# power_electronics7.net
KiCad netlist of a schematic drawn in EAGLE
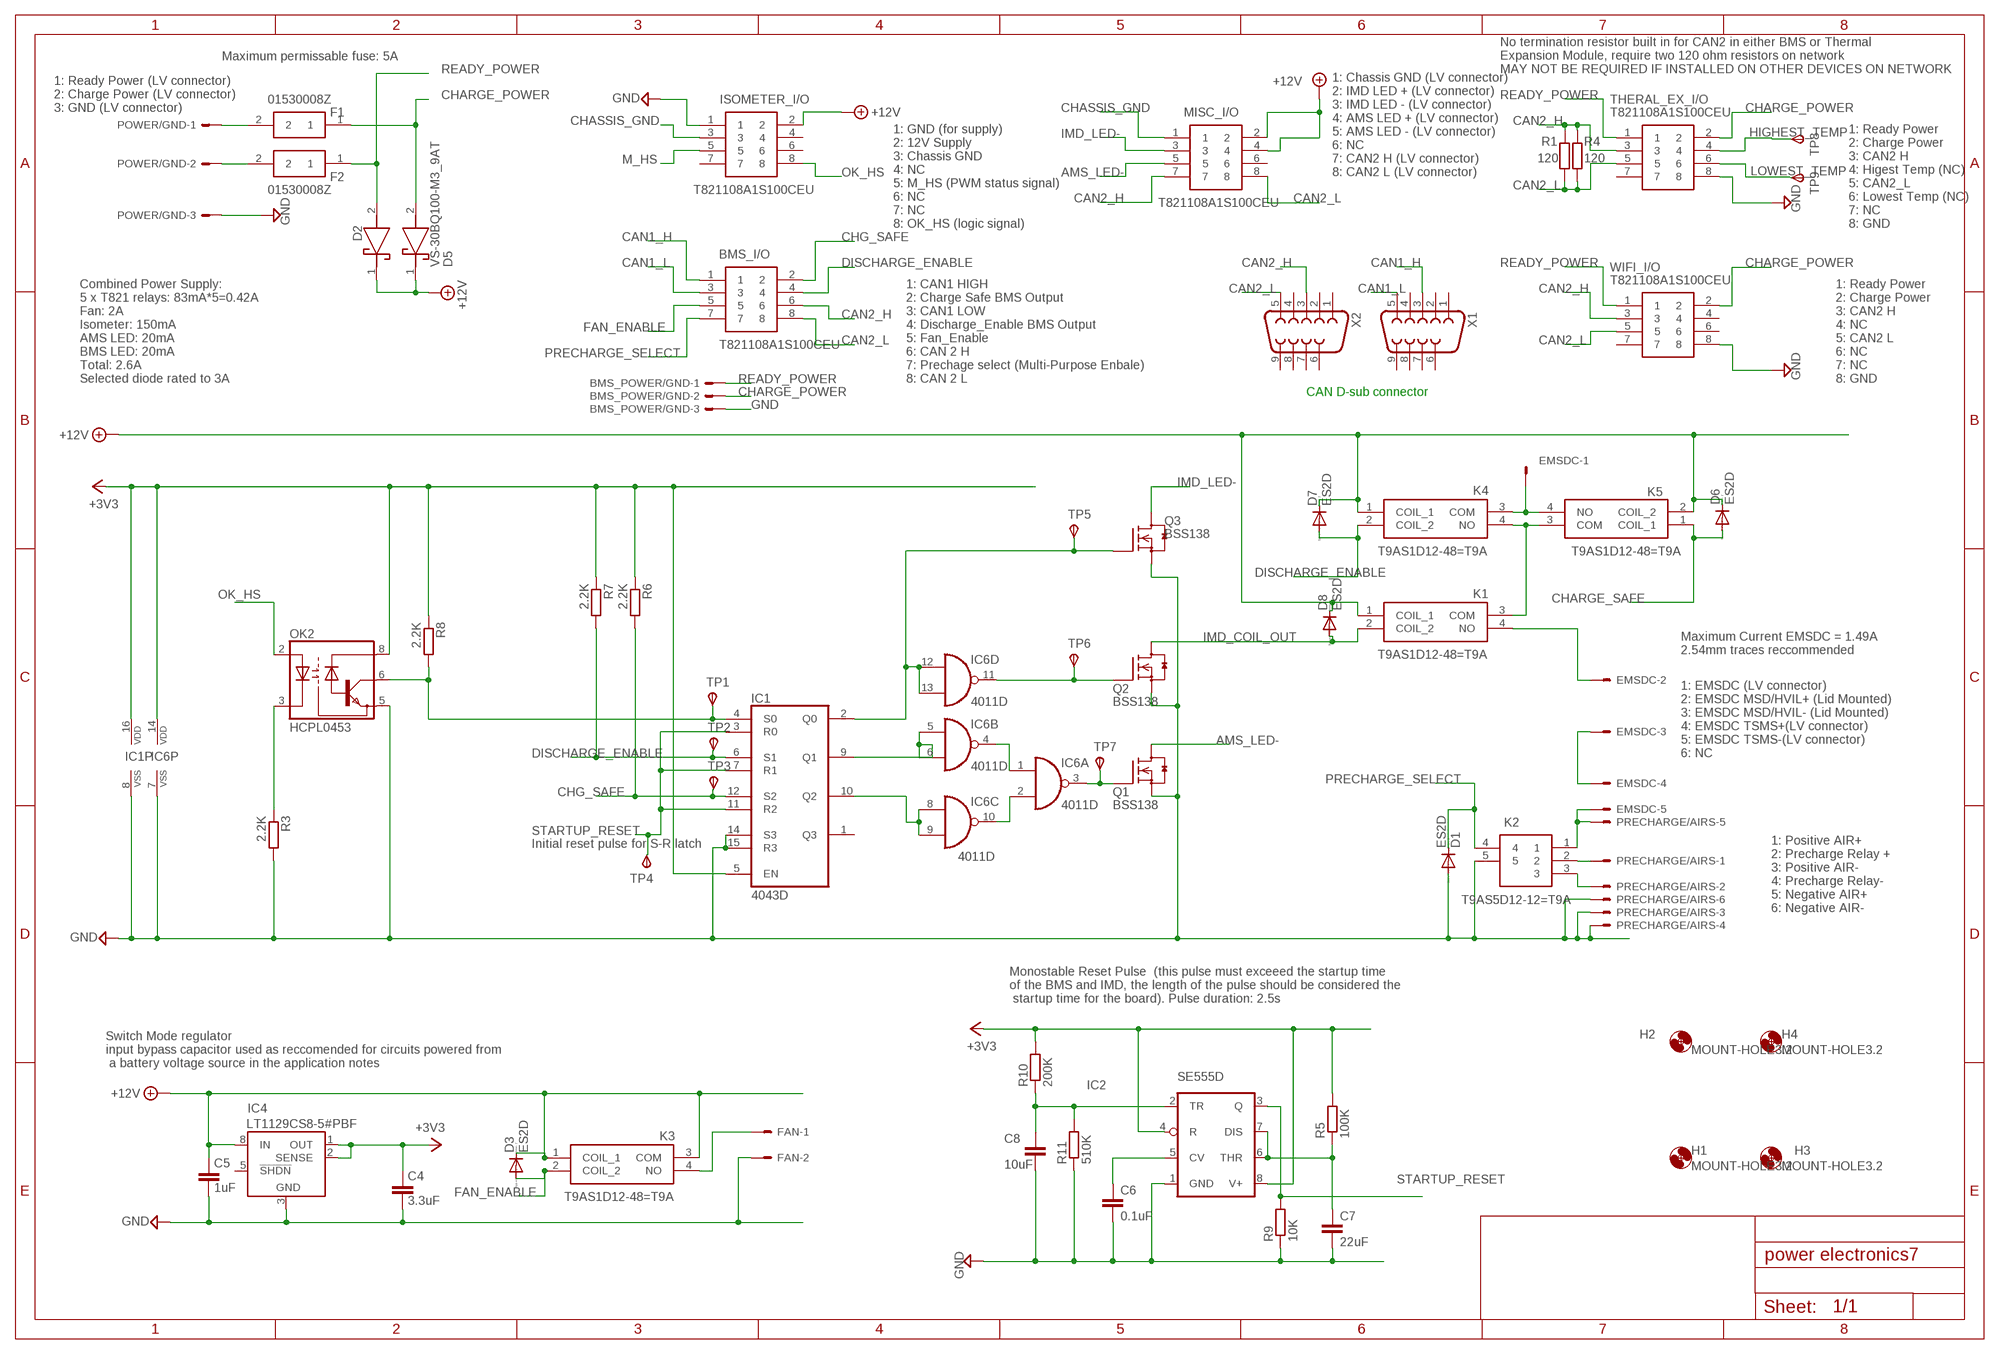
[diagram p0: schematic, sheet 1]

(export (version "E")
  (design (tool "Eeschema 10.0.6"))
  (components
    (comp (ref "BMS_I/O")
      (value "T821108A1S100CEU")
      (footprint "eagle-import:HDRV8W64P254_2X4_1778X895X915P")
      (fields (field (name "RS_PART_NUMBER") "8323569"))
      (libsource (lib "eagle-import") (part "T821108A1S100CEU"))
    )
    (comp (ref "BMS_POWER/GND")
      (value "KK-156-3")
      (footprint "eagle-import:KK-156-3")
      (fields (field (name "MF") "MOLEX"))
      (libsource (lib "eagle-import") (part "KK-156-3"))
    )
    (comp (ref "C4")
      (value "3.3uF")
      (footprint "eagle-import:C1206")
      (libsource (lib "eagle-import") (part "C-EUC1206"))
    )
    (comp (ref "C5")
      (value "1uF")
      (footprint "eagle-import:C1206")
      (libsource (lib "eagle-import") (part "C-EUC1206"))
    )
    (comp (ref "C6")
      (value "0.1uF")
      (footprint "eagle-import:C1206")
      (libsource (lib "eagle-import") (part "C-EUC1206"))
    )
    (comp (ref "C7")
      (value "22uF")
      (footprint "eagle-import:C1206")
      (libsource (lib "eagle-import") (part "C-EUC1206"))
    )
    (comp (ref "C8")
      (value "10uF")
      (footprint "eagle-import:C1206")
      (libsource (lib "eagle-import") (part "C-EUC1206"))
    )
    (comp (ref "D1")
      (value "ES2D")
      (footprint "eagle-import:SMB")
      (libsource (lib "eagle-import") (part "ES2D"))
    )
    (comp (ref "D2")
      (value "VS-30BQ100-M3_9AT")
      (footprint "eagle-import:DIOM7959X262N")
      (fields
        (field (name "MANUFACTURER_PART_NUMBER") "VS-30BQ100-M3/9AT")
        (field (name "MOUSER_PART_NUMBER") "78-VS-30BQ100-M39AT")
      )
      (libsource (lib "eagle-import") (part "VS-30BQ100-M3_9AT"))
    )
    (comp (ref "D3")
      (value "ES2D")
      (footprint "eagle-import:SMB")
      (libsource (lib "eagle-import") (part "ES2D"))
    )
    (comp (ref "D5")
      (value "VS-30BQ100-M3_9AT")
      (footprint "eagle-import:DIOM7959X262N")
      (fields
        (field (name "MANUFACTURER_PART_NUMBER") "VS-30BQ100-M3/9AT")
        (field (name "MOUSER_PART_NUMBER") "78-VS-30BQ100-M39AT")
      )
      (libsource (lib "eagle-import") (part "VS-30BQ100-M3_9AT"))
    )
    (comp (ref "D6")
      (value "ES2D")
      (footprint "eagle-import:SMB")
      (libsource (lib "eagle-import") (part "ES2D"))
    )
    (comp (ref "D7")
      (value "ES2D")
      (footprint "eagle-import:SMB")
      (libsource (lib "eagle-import") (part "ES2D"))
    )
    (comp (ref "D8")
      (value "ES2D")
      (footprint "eagle-import:SMB")
      (libsource (lib "eagle-import") (part "ES2D"))
    )
    (comp (ref "EMSDC")
      (value "KK-156-6")
      (footprint "eagle-import:KK-156-6")
      (fields (field (name "MF") "MOLEX"))
      (libsource (lib "eagle-import") (part "KK-156-6"))
    )
    (comp (ref "F1")
      (value "01530008Z")
      (footprint "eagle-import:01530008")
      (fields (field (name "RS_PART_NUMBER") "3607317"))
      (libsource (lib "eagle-import") (part "01530008Z"))
    )
    (comp (ref "F2")
      (value "01530008Z")
      (footprint "eagle-import:01530008")
      (fields (field (name "RS_PART_NUMBER") "3607317"))
      (libsource (lib "eagle-import") (part "01530008Z"))
    )
    (comp (ref "FAN")
      (value "KK-156-2")
      (footprint "eagle-import:KK-156-2")
      (fields (field (name "MF") "MOLEX"))
      (libsource (lib "eagle-import") (part "KK-156-2"))
    )
    (comp (ref "H1")
      (value "MOUNT-HOLE3.2")
      (footprint "eagle-import:3,2")
      (libsource (lib "eagle-import") (part "MOUNT-HOLE3.2"))
    )
    (comp (ref "H2")
      (value "MOUNT-HOLE3.2")
      (footprint "eagle-import:3,2")
      (libsource (lib "eagle-import") (part "MOUNT-HOLE3.2"))
    )
    (comp (ref "H3")
      (value "MOUNT-HOLE3.2")
      (footprint "eagle-import:3,2")
      (libsource (lib "eagle-import") (part "MOUNT-HOLE3.2"))
    )
    (comp (ref "H4")
      (value "MOUNT-HOLE3.2")
      (footprint "eagle-import:3,2")
      (libsource (lib "eagle-import") (part "MOUNT-HOLE3.2"))
    )
    (comp (ref "IC1")
      (value "4043D")
      (footprint "eagle-import:SO16")
      (libsource (lib "eagle-import") (part "4043D"))
    )
    (comp (ref "IC2")
      (value "SE555D")
      (footprint "eagle-import:SO08")
      (libsource (lib "eagle-import") (part "555DSE"))
    )
    (comp (ref "IC4")
      (value "LT1129CS8")
      (footprint "eagle-import:SOIC8")
      (fields (field (name "MPN") "LT1129CS8-5#PBF"))
      (libsource (lib "eagle-import") (part "LT1129CS8"))
    )
    (comp (ref "IC6")
      (value "4011D")
      (footprint "eagle-import:SO14")
      (libsource (lib "eagle-import") (part "4011D"))
    )
    (comp (ref "ISOMETER_I/O")
      (value "T821108A1S100CEU")
      (footprint "eagle-import:HDRV8W64P254_2X4_1778X895X915P")
      (fields (field (name "RS_PART_NUMBER") "8323569"))
      (libsource (lib "eagle-import") (part "T821108A1S100CEU"))
    )
    (comp (ref "K1")
      (value "T9AS1D12-48=T9A")
      (footprint "eagle-import:T9AS1D1248T9A")
      (fields (field (name "RS_PART_NUMBER") "6802534P"))
      (libsource (lib "eagle-import") (part "T9AS1D12-48=T9A"))
    )
    (comp (ref "K2")
      (value "T9AS5D12-12=T9A")
      (footprint "eagle-import:T9AS1D12")
      (fields (field (name "RS_PART_NUMBER") "6802528"))
      (libsource (lib "eagle-import") (part "T9AS5D12-12=T9A"))
    )
    (comp (ref "K3")
      (value "T9AS1D12-48=T9A")
      (footprint "eagle-import:T9AS1D1248T9A")
      (fields (field (name "RS_PART_NUMBER") "6802534P"))
      (libsource (lib "eagle-import") (part "T9AS1D12-48=T9A"))
    )
    (comp (ref "K4")
      (value "T9AS1D12-48=T9A")
      (footprint "eagle-import:T9AS1D1248T9A")
      (fields (field (name "RS_PART_NUMBER") "6802534P"))
      (libsource (lib "eagle-import") (part "T9AS1D12-48=T9A"))
    )
    (comp (ref "K5")
      (value "T9AS1D12-48=T9A")
      (footprint "eagle-import:T9AS1D1248T9A")
      (fields (field (name "RS_PART_NUMBER") "6802534P"))
      (libsource (lib "eagle-import") (part "T9AS1D12-48=T9A"))
    )
    (comp (ref "MISC_I/O")
      (value "T821108A1S100CEU")
      (footprint "eagle-import:HDRV8W64P254_2X4_1778X895X915P")
      (fields (field (name "RS_PART_NUMBER") "8323569"))
      (libsource (lib "eagle-import") (part "T821108A1S100CEU"))
    )
    (comp (ref "OK2")
      (value "HCPL0453")
      (footprint "eagle-import:SOIC08")
      (fields (field (name "MF") "AGILENT TECHNOLOGIES") (field (name "MPN") "HCPL-0453-000E"))
      (libsource (lib "eagle-import") (part "HCPL0453"))
    )
    (comp (ref "POWER/GND")
      (value "KK-156-3")
      (footprint "eagle-import:KK-156-3")
      (fields (field (name "MF") "MOLEX"))
      (libsource (lib "eagle-import") (part "KK-156-3"))
    )
    (comp (ref "PRECHARGE/AIRS")
      (value "KK-156-6")
      (footprint "eagle-import:KK-156-6")
      (fields (field (name "MF") "MOLEX"))
      (libsource (lib "eagle-import") (part "KK-156-6"))
    )
    (comp (ref "Q1")
      (value "BSS138")
      (footprint "eagle-import:SOT23")
      (libsource (lib "eagle-import") (part "BSS138"))
    )
    (comp (ref "Q2")
      (value "BSS138")
      (footprint "eagle-import:SOT23")
      (libsource (lib "eagle-import") (part "BSS138"))
    )
    (comp (ref "Q3")
      (value "BSS138")
      (footprint "eagle-import:SOT23")
      (libsource (lib "eagle-import") (part "BSS138"))
    )
    (comp (ref "R1")
      (value "120")
      (footprint "eagle-import:R1206")
      (libsource (lib "eagle-import") (part "R-EU_R1206"))
    )
    (comp (ref "R3")
      (value "2.2K")
      (footprint "eagle-import:R1206")
      (libsource (lib "eagle-import") (part "R-EU_R1206"))
    )
    (comp (ref "R4")
      (value "120")
      (footprint "eagle-import:R1206")
      (libsource (lib "eagle-import") (part "R-EU_R1206"))
    )
    (comp (ref "R5")
      (value "100K")
      (footprint "eagle-import:R1206")
      (libsource (lib "eagle-import") (part "R-EU_R1206"))
    )
    (comp (ref "R6")
      (value "2.2K")
      (footprint "eagle-import:R1206")
      (libsource (lib "eagle-import") (part "R-EU_R1206"))
    )
    (comp (ref "R7")
      (value "2.2K")
      (footprint "eagle-import:R1206")
      (libsource (lib "eagle-import") (part "R-EU_R1206"))
    )
    (comp (ref "R8")
      (value "2.2K")
      (footprint "eagle-import:R1206")
      (libsource (lib "eagle-import") (part "R-EU_R1206"))
    )
    (comp (ref "R9")
      (value "10K")
      (footprint "eagle-import:R1206")
      (libsource (lib "eagle-import") (part "R-EU_R1206"))
    )
    (comp (ref "R10")
      (value "200K")
      (footprint "eagle-import:R1206")
      (libsource (lib "eagle-import") (part "R-EU_R1206"))
    )
    (comp (ref "R11")
      (value "510K")
      (footprint "eagle-import:R1206")
      (libsource (lib "eagle-import") (part "R-EU_R1206"))
    )
    (comp (ref "THERAL_EX_I/O")
      (value "T821108A1S100CEU")
      (footprint "eagle-import:HDRV8W64P254_2X4_1778X895X915P")
      (fields (field (name "RS_PART_NUMBER") "8323569"))
      (libsource (lib "eagle-import") (part "T821108A1S100CEU"))
    )
    (comp (ref "TP1")
      (value "TPSTP11R")
      (footprint "eagle-import:TP11R")
      (libsource (lib "eagle-import") (part "TPSTP11R"))
    )
    (comp (ref "TP2")
      (value "TPSTP11R")
      (footprint "eagle-import:TP11R")
      (libsource (lib "eagle-import") (part "TPSTP11R"))
    )
    (comp (ref "TP3")
      (value "TPSTP11R")
      (footprint "eagle-import:TP11R")
      (libsource (lib "eagle-import") (part "TPSTP11R"))
    )
    (comp (ref "TP4")
      (value "TPSTP11R")
      (footprint "eagle-import:TP11R")
      (libsource (lib "eagle-import") (part "TPSTP11R"))
    )
    (comp (ref "TP5")
      (value "TPSTP11R")
      (footprint "eagle-import:TP11R")
      (libsource (lib "eagle-import") (part "TPSTP11R"))
    )
    (comp (ref "TP6")
      (value "TPSTP11R")
      (footprint "eagle-import:TP11R")
      (libsource (lib "eagle-import") (part "TPSTP11R"))
    )
    (comp (ref "TP7")
      (value "TPSTP11R")
      (footprint "eagle-import:TP11R")
      (libsource (lib "eagle-import") (part "TPSTP11R"))
    )
    (comp (ref "TP8")
      (value "TPSTP11R")
      (footprint "eagle-import:TP11R")
      (libsource (lib "eagle-import") (part "TPSTP11R"))
    )
    (comp (ref "TP9")
      (value "TPSTP11R")
      (footprint "eagle-import:TP11R")
      (libsource (lib "eagle-import") (part "TPSTP11R"))
    )
    (comp (ref "WIFI_I/O")
      (value "T821108A1S100CEU")
      (footprint "eagle-import:HDRV8W64P254_2X4_1778X895X915P")
      (fields (field (name "RS_PART_NUMBER") "8323569"))
      (libsource (lib "eagle-import") (part "T821108A1S100CEU"))
    )
    (comp (ref "X1")
      (value "F09V")
      (footprint "eagle-import:F09V")
      (libsource (lib "eagle-import") (part "F09V"))
    )
    (comp (ref "X2")
      (value "F09V")
      (footprint "eagle-import:F09V")
      (libsource (lib "eagle-import") (part "F09V"))
    )
  )
  (nets
    (net (code "1") (name "+3V3") (class "Default")
      (node (ref "C4") (pin "1") (pinfunction "1_1") (pintype "passive"))
      (node (ref "IC1") (pin "16") (pinfunction "VDD_16") (pintype "power_in"))
      (node (ref "IC1") (pin "5") (pinfunction "EN_5") (pintype "input"))
      (node (ref "IC2") (pin "4") (pinfunction "R_4") (pintype "input"))
      (node (ref "IC2") (pin "8") (pinfunction "V+_8") (pintype "power_in"))
      (node (ref "IC4") (pin "1") (pinfunction "OUT_1") (pintype "output"))
      (node (ref "IC4") (pin "2") (pinfunction "SENSE_2") (pintype "input"))
      (node (ref "IC6") (pin "14") (pinfunction "VDD_14") (pintype "power_in"))
      (node (ref "OK2") (pin "8") (pinfunction "VCC_8") (pintype "passive"))
      (node (ref "R10") (pin "2") (pinfunction "2_2") (pintype "passive"))
      (node (ref "R5") (pin "2") (pinfunction "2_2") (pintype "passive"))
      (node (ref "R6") (pin "1") (pinfunction "1_1") (pintype "passive"))
      (node (ref "R7") (pin "1") (pinfunction "1_1") (pintype "passive"))
      (node (ref "R8") (pin "1") (pinfunction "1_1") (pintype "passive"))
    )
    (net (code "2") (name "+12V") (class "Default")
      (node (ref "C5") (pin "1") (pinfunction "1_1") (pintype "passive"))
      (node (ref "D2") (pin "1") (pinfunction "K_1") (pintype "bidirectional"))
      (node (ref "D3") (pin "C") (pinfunction "C_C") (pintype "passive"))
      (node (ref "D5") (pin "1") (pinfunction "K_1") (pintype "bidirectional"))
      (node (ref "D6") (pin "C") (pinfunction "C_C") (pintype "passive"))
      (node (ref "D7") (pin "C") (pinfunction "C_C") (pintype "passive"))
      (node (ref "D8") (pin "C") (pinfunction "C_C") (pintype "passive"))
      (node (ref "IC4") (pin "8") (pinfunction "IN_8") (pintype "input"))
      (node (ref "ISOMETER_I/O") (pin "2") (pinfunction "2_2") (pintype "bidirectional"))
      (node (ref "K1") (pin "1") (pinfunction "COIL_1_1") (pintype "bidirectional"))
      (node (ref "K3") (pin "1") (pinfunction "COIL_1_1") (pintype "bidirectional"))
      (node (ref "K3") (pin "3") (pinfunction "COM_3") (pintype "bidirectional"))
      (node (ref "K4") (pin "1") (pinfunction "COIL_1_1") (pintype "bidirectional"))
      (node (ref "K5") (pin "2") (pinfunction "COIL_2_2") (pintype "bidirectional"))
      (node (ref "MISC_I/O") (pin "2") (pinfunction "2_2") (pintype "bidirectional"))
      (node (ref "MISC_I/O") (pin "4") (pinfunction "4_4") (pintype "bidirectional"))
    )
    (net (code "3") (name "/AMS_LED-") (class "Default")
      (node (ref "MISC_I/O") (pin "5") (pinfunction "5_5") (pintype "bidirectional"))
      (node (ref "Q1") (pin "3") (pinfunction "D_3") (pintype "passive"))
    )
    (net (code "4") (name "/CAN1_H") (class "Default")
      (node (ref "BMS_I/O") (pin "1") (pinfunction "1_1") (pintype "bidirectional"))
      (node (ref "X1") (pin "3") (pinfunction "3_3") (pintype "passive"))
    )
    (net (code "5") (name "/CAN1_L") (class "Default")
      (node (ref "BMS_I/O") (pin "3") (pinfunction "3_3") (pintype "bidirectional"))
      (node (ref "X1") (pin "5") (pinfunction "5_5") (pintype "passive"))
    )
    (net (code "6") (name "/CAN2_H") (class "Default")
      (node (ref "BMS_I/O") (pin "6") (pinfunction "6_6") (pintype "bidirectional"))
      (node (ref "MISC_I/O") (pin "7") (pinfunction "7_7") (pintype "bidirectional"))
      (node (ref "R1") (pin "1") (pinfunction "1_1") (pintype "passive"))
      (node (ref "R4") (pin "1") (pinfunction "1_1") (pintype "passive"))
      (node (ref "THERAL_EX_I/O") (pin "3") (pinfunction "3_3") (pintype "bidirectional"))
      (node (ref "WIFI_I/O") (pin "3") (pinfunction "3_3") (pintype "bidirectional"))
      (node (ref "X2") (pin "3") (pinfunction "3_3") (pintype "passive"))
    )
    (net (code "7") (name "/CAN2_L") (class "Default")
      (node (ref "BMS_I/O") (pin "8") (pinfunction "8_8") (pintype "bidirectional"))
      (node (ref "MISC_I/O") (pin "8") (pinfunction "8_8") (pintype "bidirectional"))
      (node (ref "R1") (pin "2") (pinfunction "2_2") (pintype "passive"))
      (node (ref "R4") (pin "2") (pinfunction "2_2") (pintype "passive"))
      (node (ref "THERAL_EX_I/O") (pin "5") (pinfunction "5_5") (pintype "bidirectional"))
      (node (ref "WIFI_I/O") (pin "5") (pinfunction "5_5") (pintype "bidirectional"))
      (node (ref "X2") (pin "5") (pinfunction "5_5") (pintype "passive"))
    )
    (net (code "8") (name "/CHARGE_POWER") (class "Default")
      (node (ref "BMS_POWER/GND") (pin "2") (pinfunction "S_2") (pintype "passive"))
      (node (ref "D5") (pin "2") (pinfunction "A_2") (pintype "bidirectional"))
      (node (ref "F1") (pin "1") (pinfunction "1_1") (pintype "bidirectional"))
      (node (ref "THERAL_EX_I/O") (pin "2") (pinfunction "2_2") (pintype "bidirectional"))
      (node (ref "WIFI_I/O") (pin "2") (pinfunction "2_2") (pintype "bidirectional"))
    )
    (net (code "9") (name "/CHARGE_SAFE") (class "Default")
      (node (ref "D6") (pin "A") (pinfunction "A_A") (pintype "passive"))
      (node (ref "K5") (pin "1") (pinfunction "COIL_1_1") (pintype "bidirectional"))
    )
    (net (code "10") (name "/CHASSIS_GND") (class "Default")
      (node (ref "ISOMETER_I/O") (pin "3") (pinfunction "3_3") (pintype "bidirectional"))
      (node (ref "MISC_I/O") (pin "1") (pinfunction "1_1") (pintype "bidirectional"))
    )
    (net (code "11") (name "/CHG_SAFE") (class "Default")
      (node (ref "BMS_I/O") (pin "2") (pinfunction "2_2") (pintype "bidirectional"))
      (node (ref "IC1") (pin "12") (pinfunction "S2_12") (pintype "input"))
      (node (ref "R6") (pin "2") (pinfunction "2_2") (pintype "passive"))
      (node (ref "TP3") (pin "TP") (pinfunction "PP_TP") (pintype "input"))
    )
    (net (code "12") (name "/DISCHARGE_ENABLE") (class "Default")
      (node (ref "BMS_I/O") (pin "4") (pinfunction "4_4") (pintype "bidirectional"))
      (node (ref "D7") (pin "A") (pinfunction "A_A") (pintype "passive"))
      (node (ref "IC1") (pin "6") (pinfunction "S1_6") (pintype "input"))
      (node (ref "K4") (pin "2") (pinfunction "COIL_2_2") (pintype "bidirectional"))
      (node (ref "R7") (pin "2") (pinfunction "2_2") (pintype "passive"))
      (node (ref "TP2") (pin "TP") (pinfunction "PP_TP") (pintype "input"))
    )
    (net (code "13") (name "/FAN_ENABLE") (class "Default")
      (node (ref "BMS_I/O") (pin "5") (pinfunction "5_5") (pintype "bidirectional"))
      (node (ref "D3") (pin "A") (pinfunction "A_A") (pintype "passive"))
      (node (ref "K3") (pin "2") (pinfunction "COIL_2_2") (pintype "bidirectional"))
    )
    (net (code "14") (name "/HIGHEST_TEMP") (class "Default")
      (node (ref "THERAL_EX_I/O") (pin "4") (pinfunction "4_4") (pintype "bidirectional"))
      (node (ref "TP8") (pin "TP") (pinfunction "PP_TP") (pintype "input"))
    )
    (net (code "15") (name "/IMD_COIL_OUT") (class "Default")
      (node (ref "D8") (pin "A") (pinfunction "A_A") (pintype "passive"))
      (node (ref "K1") (pin "2") (pinfunction "COIL_2_2") (pintype "bidirectional"))
      (node (ref "Q2") (pin "3") (pinfunction "D_3") (pintype "passive"))
    )
    (net (code "16") (name "/IMD_LED-") (class "Default")
      (node (ref "MISC_I/O") (pin "3") (pinfunction "3_3") (pintype "bidirectional"))
      (node (ref "Q3") (pin "3") (pinfunction "D_3") (pintype "passive"))
    )
    (net (code "17") (name "/LOWEST_TEMP") (class "Default")
      (node (ref "THERAL_EX_I/O") (pin "6") (pinfunction "6_6") (pintype "bidirectional"))
      (node (ref "TP9") (pin "TP") (pinfunction "PP_TP") (pintype "input"))
    )
    (net (code "18") (name "/M_HS") (class "Default")
      (node (ref "ISOMETER_I/O") (pin "5") (pinfunction "5_5") (pintype "bidirectional"))
    )
    (net (code "19") (name "/OK_HS") (class "Default")
      (node (ref "ISOMETER_I/O") (pin "8") (pinfunction "8_8") (pintype "bidirectional"))
      (node (ref "OK2") (pin "2") (pinfunction "A_2") (pintype "passive"))
    )
    (net (code "20") (name "/PRECHARGE_SELECT") (class "Default")
      (node (ref "BMS_I/O") (pin "7") (pinfunction "7_7") (pintype "bidirectional"))
      (node (ref "D1") (pin "C") (pinfunction "C_C") (pintype "passive"))
      (node (ref "K2") (pin "4") (pinfunction "4_4") (pintype "bidirectional"))
    )
    (net (code "21") (name "/READY_POWER") (class "Default")
      (node (ref "BMS_POWER/GND") (pin "1") (pinfunction "S_1") (pintype "passive"))
      (node (ref "D2") (pin "2") (pinfunction "A_2") (pintype "bidirectional"))
      (node (ref "F2") (pin "1") (pinfunction "1_1") (pintype "bidirectional"))
      (node (ref "THERAL_EX_I/O") (pin "1") (pinfunction "1_1") (pintype "bidirectional"))
      (node (ref "WIFI_I/O") (pin "1") (pinfunction "1_1") (pintype "bidirectional"))
    )
    (net (code "22") (name "/STARTUP_RESET") (class "Default")
      (node (ref "IC1") (pin "11") (pinfunction "R2_11") (pintype "input"))
      (node (ref "IC1") (pin "3") (pinfunction "R0_3") (pintype "input"))
      (node (ref "IC1") (pin "7") (pinfunction "R1_7") (pintype "input"))
      (node (ref "IC2") (pin "3") (pinfunction "Q_3") (pintype "output"))
      (node (ref "R9") (pin "2") (pinfunction "2_2") (pintype "passive"))
      (node (ref "TP4") (pin "TP") (pinfunction "PP_TP") (pintype "input"))
    )
    (net (code "23") (name "GND") (class "Default")
      (node (ref "BMS_POWER/GND") (pin "3") (pinfunction "S_3") (pintype "passive"))
      (node (ref "C4") (pin "2") (pinfunction "2_2") (pintype "passive"))
      (node (ref "C5") (pin "2") (pinfunction "2_2") (pintype "passive"))
      (node (ref "C6") (pin "2") (pinfunction "2_2") (pintype "passive"))
      (node (ref "C7") (pin "2") (pinfunction "2_2") (pintype "passive"))
      (node (ref "C8") (pin "2") (pinfunction "2_2") (pintype "passive"))
      (node (ref "D1") (pin "A") (pinfunction "A_A") (pintype "passive"))
      (node (ref "FAN") (pin "2") (pinfunction "S_2") (pintype "passive"))
      (node (ref "IC1") (pin "14") (pinfunction "S3_14") (pintype "input"))
      (node (ref "IC1") (pin "15") (pinfunction "R3_15") (pintype "input"))
      (node (ref "IC1") (pin "8") (pinfunction "VSS_8") (pintype "power_in"))
      (node (ref "IC2") (pin "1") (pinfunction "GND_1") (pintype "power_in"))
      (node (ref "IC4") (pin "3") (pinfunction "GND_3") (pintype "power_in"))
      (node (ref "IC6") (pin "7") (pinfunction "VSS_7") (pintype "power_in"))
      (node (ref "ISOMETER_I/O") (pin "1") (pinfunction "1_1") (pintype "bidirectional"))
      (node (ref "K2") (pin "5") (pinfunction "5_5") (pintype "bidirectional"))
      (node (ref "OK2") (pin "5") (pinfunction "GND_5") (pintype "passive"))
      (node (ref "POWER/GND") (pin "3") (pinfunction "S_3") (pintype "passive"))
      (node (ref "PRECHARGE/AIRS") (pin "3") (pinfunction "S_3") (pintype "passive"))
      (node (ref "PRECHARGE/AIRS") (pin "4") (pinfunction "S_4") (pintype "passive"))
      (node (ref "PRECHARGE/AIRS") (pin "6") (pinfunction "S_6") (pintype "passive"))
      (node (ref "Q1") (pin "2") (pinfunction "S_2") (pintype "passive"))
      (node (ref "Q2") (pin "2") (pinfunction "S_2") (pintype "passive"))
      (node (ref "Q3") (pin "2") (pinfunction "S_2") (pintype "passive"))
      (node (ref "R11") (pin "1") (pinfunction "1_1") (pintype "passive"))
      (node (ref "R3") (pin "2") (pinfunction "2_2") (pintype "passive"))
      (node (ref "R9") (pin "1") (pinfunction "1_1") (pintype "passive"))
      (node (ref "THERAL_EX_I/O") (pin "8") (pinfunction "8_8") (pintype "bidirectional"))
      (node (ref "WIFI_I/O") (pin "8") (pinfunction "8_8") (pintype "bidirectional"))
    )
    (net (code "24") (name "Net-(EMSDCA-S)") (class "Default")
      (node (ref "EMSDC") (pin "1") (pinfunction "S_1") (pintype "passive"))
      (node (ref "K4") (pin "3") (pinfunction "COM_3") (pintype "bidirectional"))
      (node (ref "K5") (pin "4") (pinfunction "NO_4") (pintype "bidirectional"))
    )
    (net (code "25") (name "Net-(EMSDCB-S)") (class "Default")
      (node (ref "EMSDC") (pin "2") (pinfunction "S_2") (pintype "passive"))
      (node (ref "K1") (pin "4") (pinfunction "NO_4") (pintype "bidirectional"))
    )
    (net (code "26") (name "Net-(EMSDCC-S)") (class "Default")
      (node (ref "EMSDC") (pin "3") (pinfunction "S_3") (pintype "passive"))
      (node (ref "EMSDC") (pin "4") (pinfunction "S_4") (pintype "passive"))
    )
    (net (code "27") (name "Net-(EMSDCE-S)") (class "Default")
      (node (ref "EMSDC") (pin "5") (pinfunction "S_5") (pintype "passive"))
      (node (ref "K2") (pin "1") (pinfunction "1_1") (pintype "bidirectional"))
      (node (ref "PRECHARGE/AIRS") (pin "5") (pinfunction "S_5") (pintype "passive"))
    )
    (net (code "28") (name "Net-(FANA-S)") (class "Default")
      (node (ref "FAN") (pin "1") (pinfunction "S_1") (pintype "passive"))
      (node (ref "K3") (pin "4") (pinfunction "NO_4") (pintype "bidirectional"))
    )
    (net (code "29") (name "Net-(IC1A-Q0)") (class "Default")
      (node (ref "IC1") (pin "2") (pinfunction "Q0_2") (pintype "output"))
      (node (ref "IC6") (pin "12") (pinfunction "I0_12") (pintype "input"))
      (node (ref "IC6") (pin "13") (pinfunction "I1_13") (pintype "input"))
      (node (ref "Q3") (pin "1") (pinfunction "G_1") (pintype "passive"))
      (node (ref "TP5") (pin "TP") (pinfunction "PP_TP") (pintype "input"))
    )
    (net (code "30") (name "Net-(IC1A-Q1)") (class "Default")
      (node (ref "IC1") (pin "9") (pinfunction "Q1_9") (pintype "output"))
      (node (ref "IC6") (pin "5") (pinfunction "I0_5") (pintype "input"))
      (node (ref "IC6") (pin "6") (pinfunction "I1_6") (pintype "input"))
    )
    (net (code "31") (name "Net-(IC1A-Q2)") (class "Default")
      (node (ref "IC1") (pin "10") (pinfunction "Q2_10") (pintype "output"))
      (node (ref "IC6") (pin "8") (pinfunction "I0_8") (pintype "input"))
      (node (ref "IC6") (pin "9") (pinfunction "I1_9") (pintype "input"))
    )
    (net (code "32") (name "Net-(IC1A-S0)") (class "Default")
      (node (ref "IC1") (pin "4") (pinfunction "S0_4") (pintype "input"))
      (node (ref "OK2") (pin "6") (pinfunction "VO_6") (pintype "passive"))
      (node (ref "R8") (pin "2") (pinfunction "2_2") (pintype "passive"))
      (node (ref "TP1") (pin "TP") (pinfunction "PP_TP") (pintype "input"))
    )
    (net (code "33") (name "Net-(IC2-CV)") (class "Default")
      (node (ref "C6") (pin "1") (pinfunction "1_1") (pintype "passive"))
      (node (ref "IC2") (pin "5") (pinfunction "CV_5") (pintype "input"))
    )
    (net (code "34") (name "Net-(IC2-DIS)") (class "Default")
      (node (ref "C7") (pin "1") (pinfunction "1_1") (pintype "passive"))
      (node (ref "IC2") (pin "6") (pinfunction "THR_6") (pintype "input"))
      (node (ref "IC2") (pin "7") (pinfunction "DIS_7") (pintype "input"))
      (node (ref "R5") (pin "1") (pinfunction "1_1") (pintype "passive"))
    )
    (net (code "35") (name "Net-(IC2-TR)") (class "Default")
      (node (ref "C8") (pin "1") (pinfunction "1_1") (pintype "passive"))
      (node (ref "IC2") (pin "2") (pinfunction "TR_2") (pintype "input"))
      (node (ref "R10") (pin "1") (pinfunction "1_1") (pintype "passive"))
      (node (ref "R11") (pin "2") (pinfunction "2_2") (pintype "passive"))
    )
    (net (code "36") (name "Net-(IC6A-I0)") (class "Default")
      (node (ref "IC6") (pin "1") (pinfunction "I0_1") (pintype "input"))
      (node (ref "IC6") (pin "4") (pinfunction "O_4") (pintype "output"))
    )
    (net (code "37") (name "Net-(IC6A-I1)") (class "Default")
      (node (ref "IC6") (pin "10") (pinfunction "O_10") (pintype "output"))
      (node (ref "IC6") (pin "2") (pinfunction "I1_2") (pintype "input"))
    )
    (net (code "38") (name "Net-(IC6A-O)") (class "Default")
      (node (ref "IC6") (pin "3") (pinfunction "O_3") (pintype "output"))
      (node (ref "Q1") (pin "1") (pinfunction "G_1") (pintype "passive"))
      (node (ref "TP7") (pin "TP") (pinfunction "PP_TP") (pintype "input"))
    )
    (net (code "39") (name "Net-(IC6D-O)") (class "Default")
      (node (ref "IC6") (pin "11") (pinfunction "O_11") (pintype "output"))
      (node (ref "Q2") (pin "1") (pinfunction "G_1") (pintype "passive"))
      (node (ref "TP6") (pin "TP") (pinfunction "PP_TP") (pintype "input"))
    )
    (net (code "40") (name "Net-(K1-COM)") (class "Default")
      (node (ref "K1") (pin "3") (pinfunction "COM_3") (pintype "bidirectional"))
      (node (ref "K4") (pin "4") (pinfunction "NO_4") (pintype "bidirectional"))
      (node (ref "K5") (pin "3") (pinfunction "COM_3") (pintype "bidirectional"))
    )
    (net (code "41") (name "Net-(OK2-C)") (class "Default")
      (node (ref "OK2") (pin "3") (pinfunction "C_3") (pintype "passive"))
      (node (ref "R3") (pin "1") (pinfunction "1_1") (pintype "passive"))
    )
    (net (code "42") (name "Net-(POWER/GNDA-S)") (class "Default")
      (node (ref "F1") (pin "2") (pinfunction "2_2") (pintype "bidirectional"))
      (node (ref "POWER/GND") (pin "1") (pinfunction "S_1") (pintype "passive"))
    )
    (net (code "43") (name "Net-(POWER/GNDB-S)") (class "Default")
      (node (ref "F2") (pin "2") (pinfunction "2_2") (pintype "bidirectional"))
      (node (ref "POWER/GND") (pin "2") (pinfunction "S_2") (pintype "passive"))
    )
    (net (code "44") (name "Net-(PRECHARGE/AIRSA-S)") (class "Default")
      (node (ref "K2") (pin "2") (pinfunction "2_2") (pintype "bidirectional"))
      (node (ref "PRECHARGE/AIRS") (pin "1") (pinfunction "S_1") (pintype "passive"))
    )
    (net (code "45") (name "Net-(PRECHARGE/AIRSB-S)") (class "Default")
      (node (ref "K2") (pin "3") (pinfunction "3_3") (pintype "bidirectional"))
      (node (ref "PRECHARGE/AIRS") (pin "2") (pinfunction "S_2") (pintype "passive"))
    )
    (net (code "46") (name "unconnected-(IC1A-Q3-Pad1)") (class "Default")
      (node (ref "IC1") (pin "1") (pinfunction "Q3_1") (pintype "output"))
    )
    (net (code "47") (name "unconnected-(IC4A-~{SHDN}-Pad5)") (class "Default")
      (node (ref "IC4") (pin "5") (pinfunction "~{SHDN}_5") (pintype "input"))
    )
    (net (code "48") (name "unconnected-(ISOMETER_I/O-Pad4)") (class "Default")
      (node (ref "ISOMETER_I/O") (pin "4") (pinfunction "4_4") (pintype "bidirectional"))
    )
    (net (code "49") (name "unconnected-(ISOMETER_I/O-Pad6)") (class "Default")
      (node (ref "ISOMETER_I/O") (pin "6") (pinfunction "6_6") (pintype "bidirectional"))
    )
    (net (code "50") (name "unconnected-(ISOMETER_I/O-Pad7)") (class "Default")
      (node (ref "ISOMETER_I/O") (pin "7") (pinfunction "7_7") (pintype "bidirectional"))
    )
    (net (code "51") (name "unconnected-(MISC_I/O-Pad6)") (class "Default")
      (node (ref "MISC_I/O") (pin "6") (pinfunction "6_6") (pintype "bidirectional"))
    )
    (net (code "52") (name "unconnected-(THERAL_EX_I/O-Pad7)") (class "Default")
      (node (ref "THERAL_EX_I/O") (pin "7") (pinfunction "7_7") (pintype "bidirectional"))
    )
    (net (code "53") (name "unconnected-(WIFI_I/O-Pad4)") (class "Default")
      (node (ref "WIFI_I/O") (pin "4") (pinfunction "4_4") (pintype "bidirectional"))
    )
    (net (code "54") (name "unconnected-(WIFI_I/O-Pad6)") (class "Default")
      (node (ref "WIFI_I/O") (pin "6") (pinfunction "6_6") (pintype "bidirectional"))
    )
    (net (code "55") (name "unconnected-(WIFI_I/O-Pad7)") (class "Default")
      (node (ref "WIFI_I/O") (pin "7") (pinfunction "7_7") (pintype "bidirectional"))
    )
    (net (code "56") (name "unconnected-(X1-Pad1)") (class "Default")
      (node (ref "X1") (pin "1") (pinfunction "1_1") (pintype "passive"))
    )
    (net (code "57") (name "unconnected-(X1-Pad2)") (class "Default")
      (node (ref "X1") (pin "2") (pinfunction "2_2") (pintype "passive"))
    )
    (net (code "58") (name "unconnected-(X1-Pad4)") (class "Default")
      (node (ref "X1") (pin "4") (pinfunction "4_4") (pintype "passive"))
    )
    (net (code "59") (name "unconnected-(X1-Pad6)") (class "Default")
      (node (ref "X1") (pin "6") (pinfunction "6_6") (pintype "passive"))
    )
    (net (code "60") (name "unconnected-(X1-Pad7)") (class "Default")
      (node (ref "X1") (pin "7") (pinfunction "7_7") (pintype "passive"))
    )
    (net (code "61") (name "unconnected-(X1-Pad8)") (class "Default")
      (node (ref "X1") (pin "8") (pinfunction "8_8") (pintype "passive"))
    )
    (net (code "62") (name "unconnected-(X1-Pad9)") (class "Default")
      (node (ref "X1") (pin "9") (pinfunction "9_9") (pintype "passive"))
    )
    (net (code "63") (name "unconnected-(X2-Pad1)") (class "Default")
      (node (ref "X2") (pin "1") (pinfunction "1_1") (pintype "passive"))
    )
    (net (code "64") (name "unconnected-(X2-Pad2)") (class "Default")
      (node (ref "X2") (pin "2") (pinfunction "2_2") (pintype "passive"))
    )
    (net (code "65") (name "unconnected-(X2-Pad4)") (class "Default")
      (node (ref "X2") (pin "4") (pinfunction "4_4") (pintype "passive"))
    )
    (net (code "66") (name "unconnected-(X2-Pad6)") (class "Default")
      (node (ref "X2") (pin "6") (pinfunction "6_6") (pintype "passive"))
    )
    (net (code "67") (name "unconnected-(X2-Pad7)") (class "Default")
      (node (ref "X2") (pin "7") (pinfunction "7_7") (pintype "passive"))
    )
    (net (code "68") (name "unconnected-(X2-Pad8)") (class "Default")
      (node (ref "X2") (pin "8") (pinfunction "8_8") (pintype "passive"))
    )
    (net (code "69") (name "unconnected-(X2-Pad9)") (class "Default")
      (node (ref "X2") (pin "9") (pinfunction "9_9") (pintype "passive"))
    )
  )
)
